# PMIC.net
KiCad netlist of a schematic drawn in Altium Designer
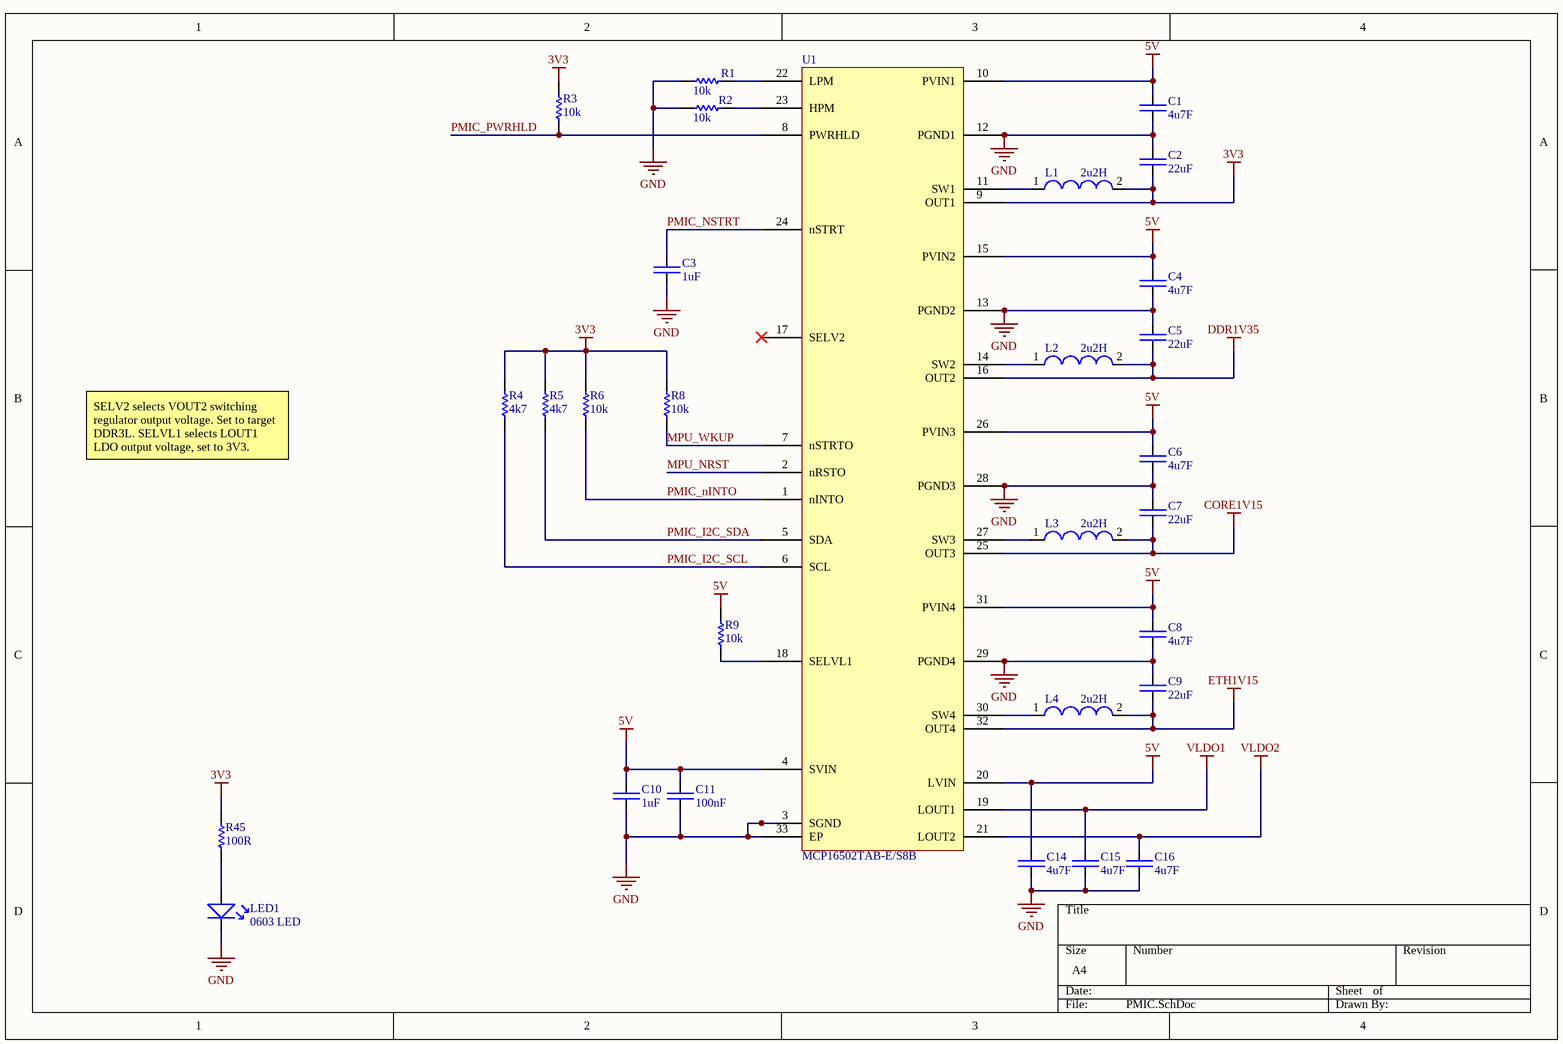
[diagram p0: PMIC.SchDoc]

(export (version "E")
  (design (tool "Eeschema 10.0.6"))
  (components
    (comp (ref "C1")
      (value "4u7F")
      (footprint "CAP-0805")
      (description "Capacitor chip unpolarized. 0805")
      (libsource (lib "Master") (part "CAP-0805"))
    )
    (comp (ref "C2")
      (value "22uF")
      (footprint "CAP-1206")
      (description "Capacitor chip unpolarized. 1206")
      (libsource (lib "Master") (part "CAP-1206"))
    )
    (comp (ref "C3")
      (value "1uF")
      (footprint "CAP-0805")
      (description "Capacitor chip unpolarized. 0805")
      (libsource (lib "Master") (part "CAP-0805"))
    )
    (comp (ref "C4")
      (value "4u7F")
      (footprint "CAP-0805")
      (description "Capacitor chip unpolarized. 0805")
      (libsource (lib "Master") (part "CAP-0805"))
    )
    (comp (ref "C5")
      (value "22uF")
      (footprint "CAP-1206")
      (description "Capacitor chip unpolarized. 1206")
      (libsource (lib "Master") (part "CAP-1206"))
    )
    (comp (ref "C6")
      (value "4u7F")
      (footprint "CAP-0805")
      (description "Capacitor chip unpolarized. 0805")
      (libsource (lib "Master") (part "CAP-0805"))
    )
    (comp (ref "C7")
      (value "22uF")
      (footprint "CAP-1206")
      (description "Capacitor chip unpolarized. 1206")
      (libsource (lib "Master") (part "CAP-1206"))
    )
    (comp (ref "C8")
      (value "4u7F")
      (footprint "CAP-0805")
      (description "Capacitor chip unpolarized. 0805")
      (libsource (lib "Master") (part "CAP-0805"))
    )
    (comp (ref "C9")
      (value "22uF")
      (footprint "CAP-1206")
      (description "Capacitor chip unpolarized. 1206")
      (libsource (lib "Master") (part "CAP-1206"))
    )
    (comp (ref "C10")
      (value "1uF")
      (footprint "CAP-0805")
      (description "Capacitor chip unpolarized. 0805")
      (libsource (lib "Master") (part "CAP-0805"))
    )
    (comp (ref "C11")
      (value "100nF")
      (footprint "CAP-0603")
      (description "Capacitor chip unpolarized. 0603")
      (libsource (lib "Master") (part "CAP-0603"))
    )
    (comp (ref "C14")
      (value "4u7F")
      (footprint "CAP-0805")
      (description "Capacitor chip unpolarized. 0805")
      (libsource (lib "Master") (part "CAP-0805"))
    )
    (comp (ref "C15")
      (value "4u7F")
      (footprint "CAP-0805")
      (description "Capacitor chip unpolarized. 0805")
      (libsource (lib "Master") (part "CAP-0805"))
    )
    (comp (ref "C16")
      (value "4u7F")
      (footprint "CAP-0805")
      (description "Capacitor chip unpolarized. 0805")
      (libsource (lib "Master") (part "CAP-0805"))
    )
    (comp (ref "L1") (value "2u2H") (footprint "IND-1210") (libsource (lib "Master") (part "IND-1210")))
    (comp (ref "L2") (value "2u2H") (footprint "IND-1210") (libsource (lib "Master") (part "IND-1210")))
    (comp (ref "L3") (value "2u2H") (footprint "IND-1210") (libsource (lib "Master") (part "IND-1210")))
    (comp (ref "L4") (value "2u2H") (footprint "IND-1210") (libsource (lib "Master") (part "IND-1210")))
    (comp (ref "LED1") (value "0603 LED") (footprint "0603 LED") (libsource (lib "Master") (part "0603 LED")))
    (comp (ref "R1")
      (value "10k")
      (footprint "RES-0603")
      (description "Resistor chip. 0603")
      (libsource (lib "Master") (part "RES-0603"))
    )
    (comp (ref "R2")
      (value "10k")
      (footprint "RES-0603")
      (description "Resistor chip. 0603")
      (libsource (lib "Master") (part "RES-0603"))
    )
    (comp (ref "R3")
      (value "10k")
      (footprint "RES-0603")
      (description "Resistor chip. 0603")
      (libsource (lib "Master") (part "RES-0603"))
    )
    (comp (ref "R4")
      (value "4k7")
      (footprint "RES-0603")
      (description "Resistor chip. 0603")
      (libsource (lib "Master") (part "RES-0603"))
    )
    (comp (ref "R5")
      (value "4k7")
      (footprint "RES-0603")
      (description "Resistor chip. 0603")
      (libsource (lib "Master") (part "RES-0603"))
    )
    (comp (ref "R6")
      (value "10k")
      (footprint "RES-0603")
      (description "Resistor chip. 0603")
      (libsource (lib "Master") (part "RES-0603"))
    )
    (comp (ref "R8")
      (value "10k")
      (footprint "RES-0603")
      (description "Resistor chip. 0603")
      (libsource (lib "Master") (part "RES-0603"))
    )
    (comp (ref "R9")
      (value "10k")
      (footprint "RES-0603")
      (description "Resistor chip. 0603")
      (libsource (lib "Master") (part "RES-0603"))
    )
    (comp (ref "R45")
      (value "100R")
      (footprint "RES-0603")
      (description "Resistor chip. 0603")
      (libsource (lib "Master") (part "RES-0603"))
    )
    (comp (ref "U1")
      (value "MCP16502TAB-E/S8B")
      (footprint "MCP16502TAB-E/S8B")
      (description "Microchip PMIC for SAM9X devices")
      (libsource (lib "Master") (part "MCP16502TAB-E/S8B"))
    )
  )
  (nets
    (net (code "1") (name "/MPU_NRST") (class "Default")
      (node (ref "U1") (pin "2") (pinfunction "nRSTO_2") (pintype "passive"))
    )
    (net (code "2") (name "/MPU_WKUP") (class "Default")
      (node (ref "R8") (pin "1") (pintype "passive"))
      (node (ref "U1") (pin "7") (pinfunction "nSTRTO_7") (pintype "passive"))
    )
    (net (code "3") (name "/PMIC_I2C_SCL") (class "Default")
      (node (ref "R4") (pin "1") (pintype "passive"))
      (node (ref "U1") (pin "6") (pinfunction "SCL_6") (pintype "passive"))
    )
    (net (code "4") (name "/PMIC_I2C_SDA") (class "Default")
      (node (ref "R5") (pin "1") (pintype "passive"))
      (node (ref "U1") (pin "5") (pinfunction "SDA_5") (pintype "passive"))
    )
    (net (code "5") (name "/PMIC_NSTRT") (class "Default")
      (node (ref "C3") (pin "2") (pintype "passive"))
      (node (ref "U1") (pin "24") (pinfunction "nSTRT_24") (pintype "passive"))
    )
    (net (code "6") (name "/PMIC_PWRHLD") (class "Default")
      (node (ref "R3") (pin "2") (pintype "passive"))
      (node (ref "U1") (pin "8") (pinfunction "PWRHLD_8") (pintype "passive"))
    )
    (net (code "7") (name "/PMIC_nINTO") (class "Default")
      (node (ref "R6") (pin "1") (pintype "passive"))
      (node (ref "U1") (pin "1") (pinfunction "nINTO_1") (pintype "passive"))
    )
    (net (code "8") (name "3V3") (class "Default")
      (node (ref "C2") (pin "1") (pintype "passive"))
      (node (ref "L1") (pin "2") (pintype "passive"))
      (node (ref "R3") (pin "1") (pintype "passive"))
      (node (ref "R4") (pin "2") (pintype "passive"))
      (node (ref "R45") (pin "2") (pintype "passive"))
      (node (ref "R5") (pin "2") (pintype "passive"))
      (node (ref "R6") (pin "2") (pintype "passive"))
      (node (ref "R8") (pin "2") (pintype "passive"))
      (node (ref "U1") (pin "9") (pinfunction "OUT1_9") (pintype "passive"))
    )
    (net (code "9") (name "5V") (class "Default")
      (node (ref "C1") (pin "2") (pintype "passive"))
      (node (ref "C10") (pin "2") (pintype "passive"))
      (node (ref "C11") (pin "2") (pintype "passive"))
      (node (ref "C14") (pin "2") (pintype "passive"))
      (node (ref "C4") (pin "2") (pintype "passive"))
      (node (ref "C6") (pin "2") (pintype "passive"))
      (node (ref "C8") (pin "2") (pintype "passive"))
      (node (ref "R9") (pin "2") (pintype "passive"))
      (node (ref "U1") (pin "10") (pinfunction "PVIN1_10") (pintype "passive"))
      (node (ref "U1") (pin "15") (pinfunction "PVIN2_15") (pintype "passive"))
      (node (ref "U1") (pin "20") (pinfunction "LVIN_20") (pintype "passive"))
      (node (ref "U1") (pin "26") (pinfunction "PVIN3_26") (pintype "passive"))
      (node (ref "U1") (pin "31") (pinfunction "PVIN4_31") (pintype "passive"))
      (node (ref "U1") (pin "4") (pinfunction "SVIN_4") (pintype "passive"))
    )
    (net (code "10") (name "CORE1V15") (class "Default")
      (node (ref "C7") (pin "1") (pintype "passive"))
      (node (ref "L3") (pin "2") (pintype "passive"))
      (node (ref "U1") (pin "25") (pinfunction "OUT3_25") (pintype "passive"))
    )
    (net (code "11") (name "DDR1V35") (class "Default")
      (node (ref "C5") (pin "1") (pintype "passive"))
      (node (ref "L2") (pin "2") (pintype "passive"))
      (node (ref "U1") (pin "16") (pinfunction "OUT2_16") (pintype "passive"))
    )
    (net (code "12") (name "ETH1V15") (class "Default")
      (node (ref "C9") (pin "1") (pintype "passive"))
      (node (ref "L4") (pin "2") (pintype "passive"))
      (node (ref "U1") (pin "32") (pinfunction "OUT4_32") (pintype "passive"))
    )
    (net (code "13") (name "GND") (class "Default")
      (node (ref "C1") (pin "1") (pintype "passive"))
      (node (ref "C10") (pin "1") (pintype "passive"))
      (node (ref "C11") (pin "1") (pintype "passive"))
      (node (ref "C14") (pin "1") (pintype "passive"))
      (node (ref "C15") (pin "1") (pintype "passive"))
      (node (ref "C16") (pin "1") (pintype "passive"))
      (node (ref "C2") (pin "2") (pintype "passive"))
      (node (ref "C3") (pin "1") (pintype "passive"))
      (node (ref "C4") (pin "1") (pintype "passive"))
      (node (ref "C5") (pin "2") (pintype "passive"))
      (node (ref "C6") (pin "1") (pintype "passive"))
      (node (ref "C7") (pin "2") (pintype "passive"))
      (node (ref "C8") (pin "1") (pintype "passive"))
      (node (ref "C9") (pin "2") (pintype "passive"))
      (node (ref "LED1") (pin "2") (pinfunction "5_2") (pintype "passive"))
      (node (ref "R1") (pin "2") (pintype "passive"))
      (node (ref "R2") (pin "2") (pintype "passive"))
      (node (ref "U1") (pin "12") (pinfunction "PGND1_12") (pintype "passive"))
      (node (ref "U1") (pin "13") (pinfunction "PGND2_13") (pintype "passive"))
      (node (ref "U1") (pin "28") (pinfunction "PGND3_28") (pintype "passive"))
      (node (ref "U1") (pin "29") (pinfunction "PGND4_29") (pintype "passive"))
      (node (ref "U1") (pin "3") (pinfunction "SGND_3") (pintype "passive"))
      (node (ref "U1") (pin "33") (pinfunction "EP_33") (pintype "passive"))
    )
    (net (code "14") (name "Net-(LED1-6)") (class "Default")
      (node (ref "LED1") (pin "1") (pinfunction "6_1") (pintype "passive"))
      (node (ref "R45") (pin "1") (pintype "passive"))
    )
    (net (code "15") (name "Net-(U1-HPM)") (class "Default")
      (node (ref "R2") (pin "1") (pintype "passive"))
      (node (ref "U1") (pin "23") (pinfunction "HPM_23") (pintype "passive"))
    )
    (net (code "16") (name "Net-(U1-LPM)") (class "Default")
      (node (ref "R1") (pin "1") (pintype "passive"))
      (node (ref "U1") (pin "22") (pinfunction "LPM_22") (pintype "passive"))
    )
    (net (code "17") (name "Net-(U1-SELVL1)") (class "Default")
      (node (ref "R9") (pin "1") (pintype "passive"))
      (node (ref "U1") (pin "18") (pinfunction "SELVL1_18") (pintype "passive"))
    )
    (net (code "18") (name "Net-(U1-SW1)") (class "Default")
      (node (ref "L1") (pin "1") (pintype "passive"))
      (node (ref "U1") (pin "11") (pinfunction "SW1_11") (pintype "passive"))
    )
    (net (code "19") (name "Net-(U1-SW2)") (class "Default")
      (node (ref "L2") (pin "1") (pintype "passive"))
      (node (ref "U1") (pin "14") (pinfunction "SW2_14") (pintype "passive"))
    )
    (net (code "20") (name "Net-(U1-SW3)") (class "Default")
      (node (ref "L3") (pin "1") (pintype "passive"))
      (node (ref "U1") (pin "27") (pinfunction "SW3_27") (pintype "passive"))
    )
    (net (code "21") (name "Net-(U1-SW4)") (class "Default")
      (node (ref "L4") (pin "1") (pintype "passive"))
      (node (ref "U1") (pin "30") (pinfunction "SW4_30") (pintype "passive"))
    )
    (net (code "22") (name "VLDO1") (class "Default")
      (node (ref "C15") (pin "2") (pintype "passive"))
      (node (ref "U1") (pin "19") (pinfunction "LOUT1_19") (pintype "passive"))
    )
    (net (code "23") (name "VLDO2") (class "Default")
      (node (ref "C16") (pin "2") (pintype "passive"))
      (node (ref "U1") (pin "21") (pinfunction "LOUT2_21") (pintype "passive"))
    )
    (net (code "24") (name "unconnected-(U1-SELV2-Pad17)") (class "Default")
      (node (ref "U1") (pin "17") (pinfunction "SELV2_17") (pintype "passive+no_connect"))
    )
  )
)
